# charger_and_dc_dc_ctrl.net
KiCad netlist of a schematic drawn in EAGLE
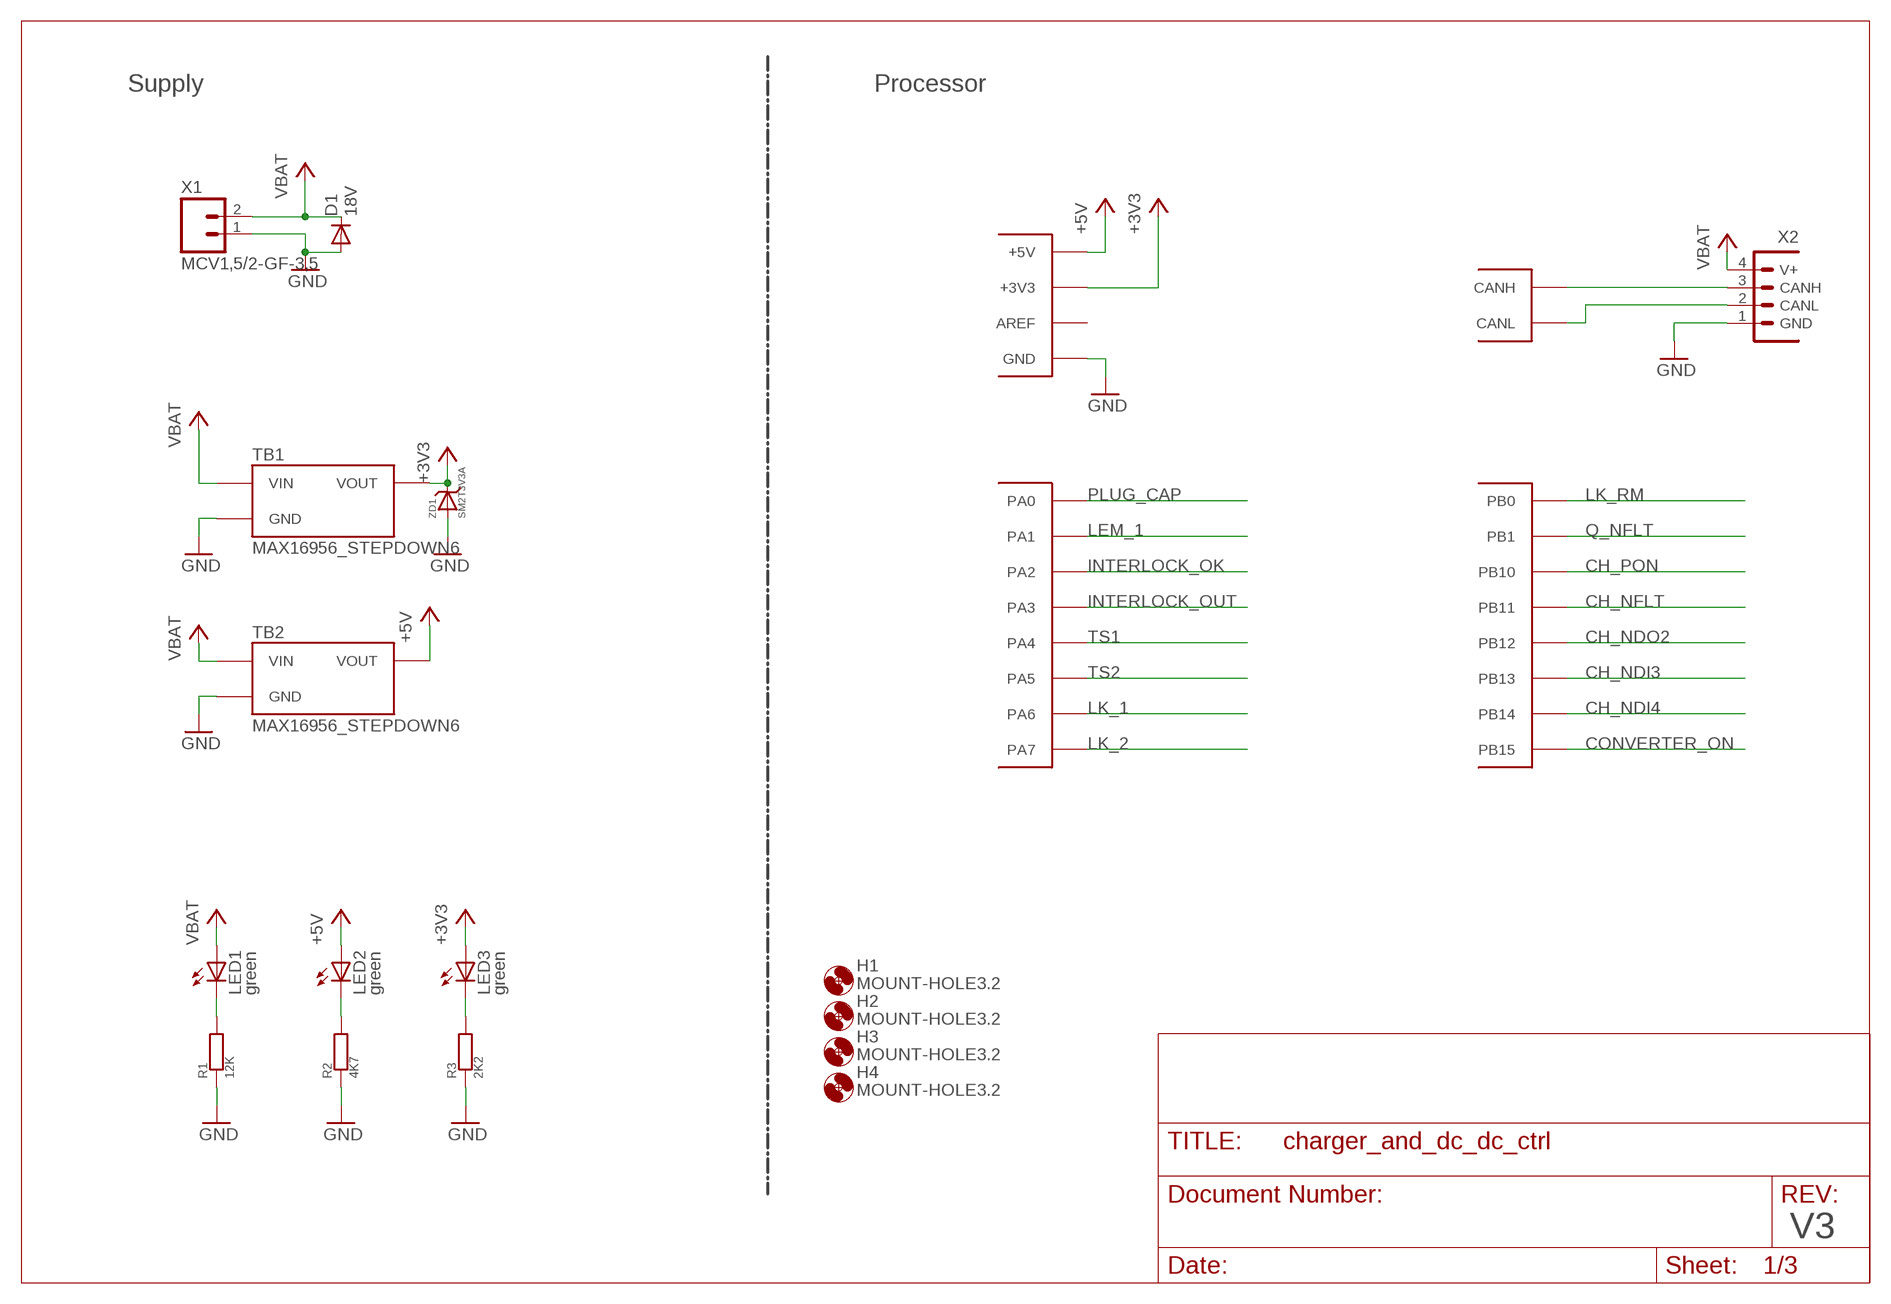
[diagram p0: schematic, sheet 1]
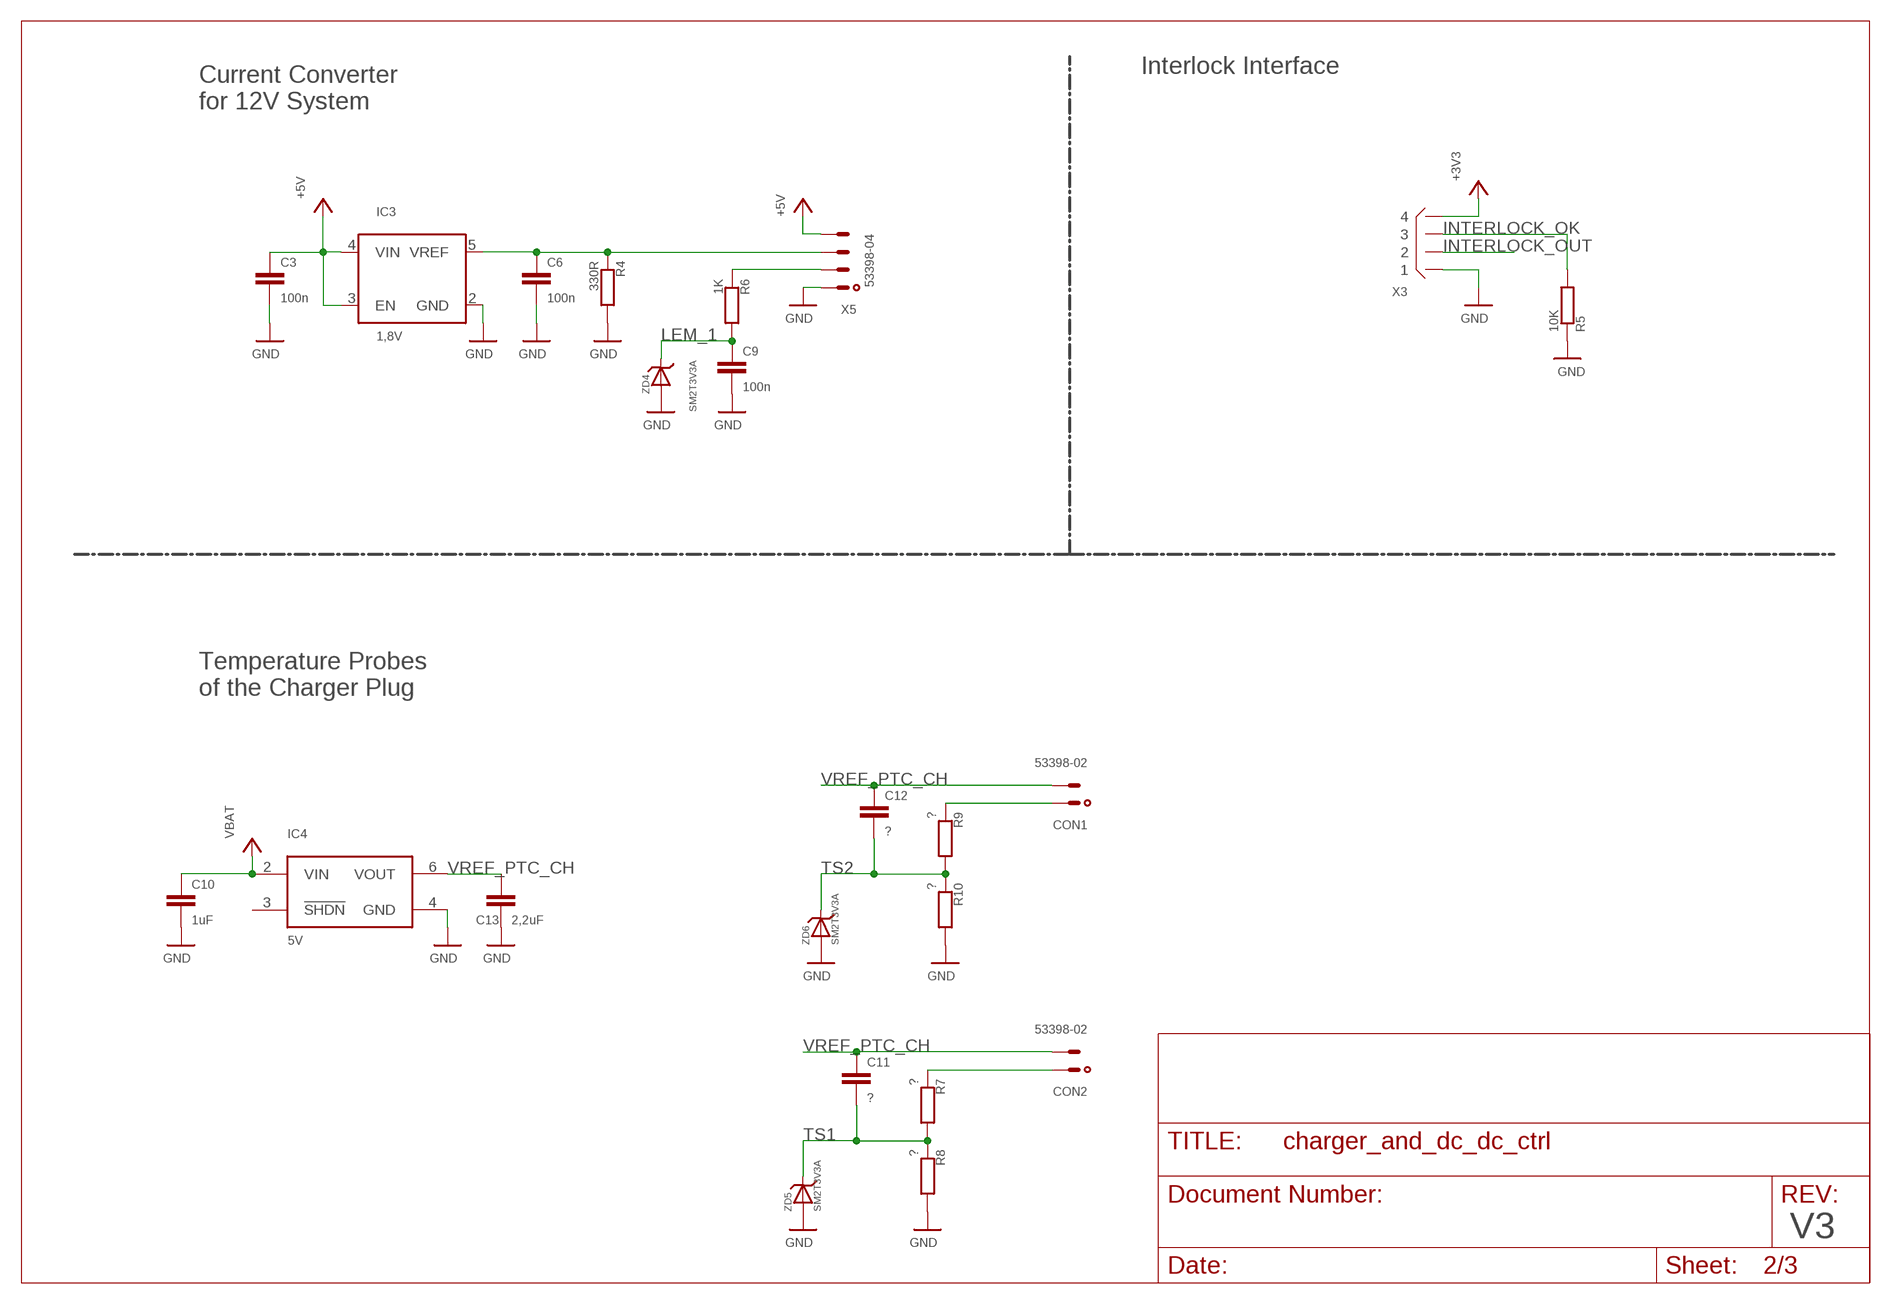
[diagram p1: schematic, sheet 2]
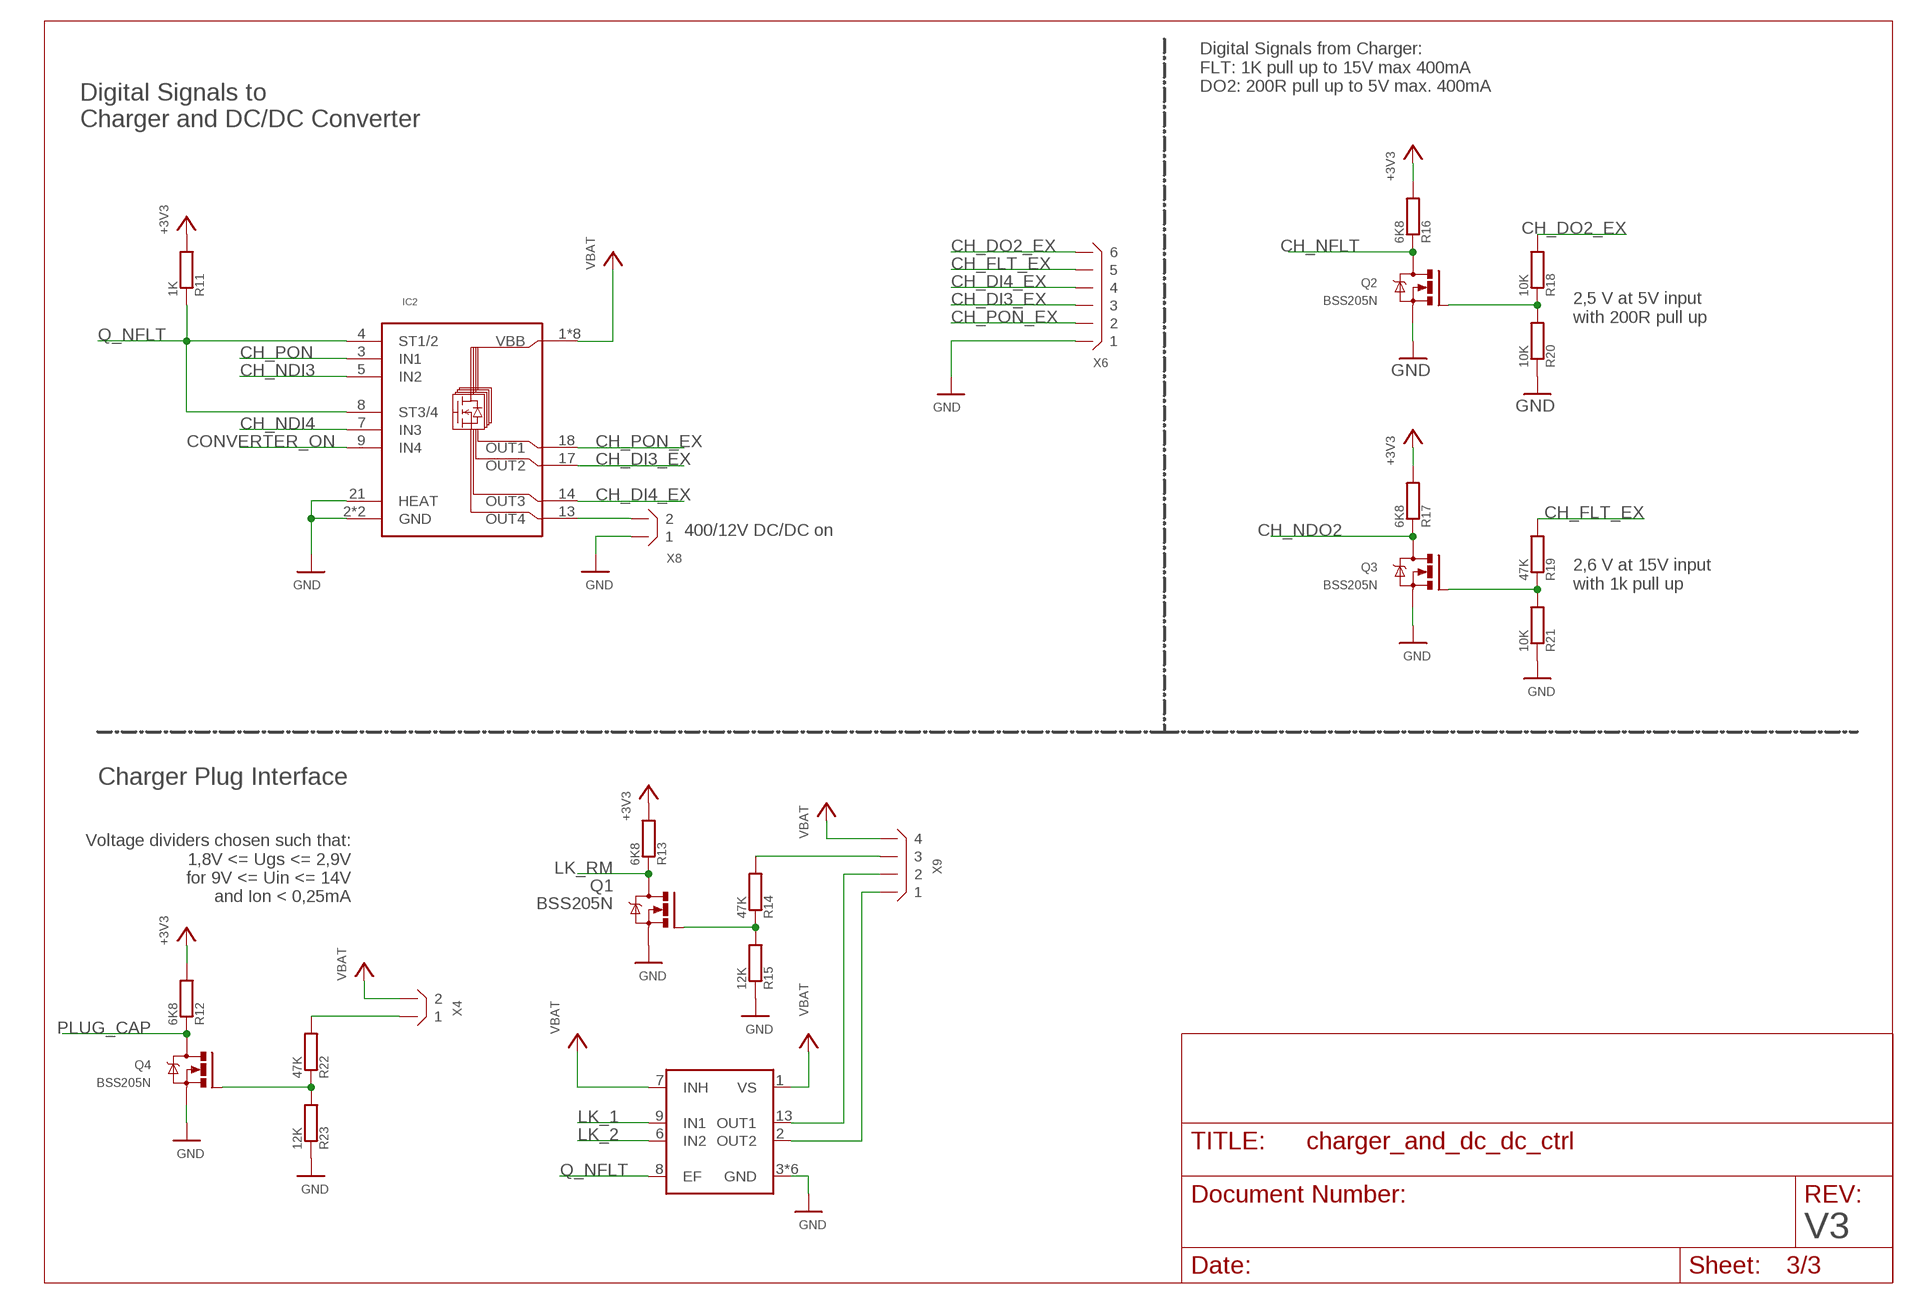
[diagram p2: schematic, sheet 3]

(export (version "E")
  (design (tool "Eeschema 10.0.6"))
  (components
    (comp (ref "CANIO_1")
      (value "STM32F103XX_CAN-IO-EXPANDERC")
      (footprint "eagle-import:STM32F103XX_CANIO-EXPANDER3")
      (libsource (lib "eagle-import") (part "STM32F103XX_CAN-IO-EXPANDERC"))
    )
    (comp (ref "D1")
      (value "18V")
      (footprint "eagle-import:DO214AA")
      (libsource (lib "eagle-import") (part "DIODE-DO214AA"))
    )
    (comp (ref "H1")
      (value "MOUNT-HOLE3.2")
      (footprint "eagle-import:3,2")
      (libsource (lib "eagle-import") (part "MOUNT-HOLE3.2"))
    )
    (comp (ref "H2")
      (value "MOUNT-HOLE3.2")
      (footprint "eagle-import:3,2")
      (libsource (lib "eagle-import") (part "MOUNT-HOLE3.2"))
    )
    (comp (ref "H3")
      (value "MOUNT-HOLE3.2")
      (footprint "eagle-import:3,2")
      (libsource (lib "eagle-import") (part "MOUNT-HOLE3.2"))
    )
    (comp (ref "H4")
      (value "MOUNT-HOLE3.2")
      (footprint "eagle-import:3,2")
      (libsource (lib "eagle-import") (part "MOUNT-HOLE3.2"))
    )
    (comp (ref "LED1")
      (value "green")
      (footprint "eagle-import:CHIP-LED0805")
      (libsource (lib "eagle-import") (part "LEDCHIP-LED0805"))
    )
    (comp (ref "LED2")
      (value "green")
      (footprint "eagle-import:CHIP-LED0805")
      (libsource (lib "eagle-import") (part "LEDCHIP-LED0805"))
    )
    (comp (ref "LED3")
      (value "green")
      (footprint "eagle-import:CHIP-LED0805")
      (libsource (lib "eagle-import") (part "LEDCHIP-LED0805"))
    )
    (comp (ref "R1")
      (value "12K")
      (footprint "eagle-import:R0805")
      (libsource (lib "eagle-import") (part "R"))
    )
    (comp (ref "R2")
      (value "4K7")
      (footprint "eagle-import:R0805")
      (libsource (lib "eagle-import") (part "R"))
    )
    (comp (ref "R3")
      (value "2K2")
      (footprint "eagle-import:R0805")
      (libsource (lib "eagle-import") (part "R"))
    )
    (comp (ref "TB1")
      (value "MAX16956_STEPDOWN6")
      (footprint "eagle-import:MAX16956_STEPDOWN6")
      (libsource (lib "eagle-import") (part "MAX16956_STEPDOWN6"))
    )
    (comp (ref "TB2")
      (value "MAX16956_STEPDOWN6")
      (footprint "eagle-import:MAX16956_STEPDOWN6")
      (libsource (lib "eagle-import") (part "MAX16956_STEPDOWN6"))
    )
    (comp (ref "X1")
      (value "MCV1,5/2-GF-3,5")
      (footprint "eagle-import:MCV1,5_2-GF-3,5")
      (libsource (lib "eagle-import") (part "MCV1,5/2-GF-3,5"))
    )
    (comp (ref "X2")
      (value "CIOC_4-1-FV-A_CAN-BELEGUNG")
      (footprint "eagle-import:CIOC_4-1-FV")
      (libsource (lib "eagle-import") (part "CIOC_4-1-FV-A_CAN-BELEGUNG"))
    )
    (comp (ref "ZD1")
      (value "SM2T3V3A")
      (footprint "eagle-import:SM2T3V3A")
      (libsource (lib "eagle-import") (part "SM2T3V3A"))
    )
    (comp (ref "IC2")
      (value "BTS716G-NEWM")
      (footprint "eagle-import:INF-PG-DSO-20-30_M_1PRIMARY")
      (libsource (lib "eagle-import") (part "BTS716G-NEWM"))
    )
    (comp (ref "IC6")
      (value "TLE4207GN")
      (footprint "eagle-import:INF-PG-DSO-14-22_N_1PRIMARY")
      (libsource (lib "eagle-import") (part "TLE4207GN"))
    )
    (comp (ref "Q1")
      (value "BSS205N")
      (footprint "eagle-import:SOT23")
      (libsource (lib "eagle-import") (part "BSS205N"))
    )
    (comp (ref "Q2")
      (value "BSS205N")
      (footprint "eagle-import:SOT23")
      (libsource (lib "eagle-import") (part "BSS205N"))
    )
    (comp (ref "Q3")
      (value "BSS205N")
      (footprint "eagle-import:SOT23")
      (libsource (lib "eagle-import") (part "BSS205N"))
    )
    (comp (ref "Q4")
      (value "BSS205N")
      (footprint "eagle-import:SOT23")
      (libsource (lib "eagle-import") (part "BSS205N"))
    )
    (comp (ref "R11")
      (value "1K")
      (footprint "eagle-import:R0603")
      (libsource (lib "eagle-import") (part "R0603"))
    )
    (comp (ref "R12")
      (value "6K8")
      (footprint "eagle-import:R0603")
      (libsource (lib "eagle-import") (part "R0603"))
    )
    (comp (ref "R13")
      (value "6K8")
      (footprint "eagle-import:R0805")
      (libsource (lib "eagle-import") (part "R"))
    )
    (comp (ref "R14")
      (value "47K")
      (footprint "eagle-import:R0805")
      (libsource (lib "eagle-import") (part "R"))
    )
    (comp (ref "R15")
      (value "12K")
      (footprint "eagle-import:R0805")
      (libsource (lib "eagle-import") (part "R"))
    )
    (comp (ref "R16")
      (value "6K8")
      (footprint "eagle-import:R0603")
      (libsource (lib "eagle-import") (part "R0603"))
    )
    (comp (ref "R17")
      (value "6K8")
      (footprint "eagle-import:R0603")
      (libsource (lib "eagle-import") (part "R0603"))
    )
    (comp (ref "R18")
      (value "10K")
      (footprint "eagle-import:R0603")
      (libsource (lib "eagle-import") (part "R0603"))
    )
    (comp (ref "R19")
      (value "47K")
      (footprint "eagle-import:R0603")
      (libsource (lib "eagle-import") (part "R0603"))
    )
    (comp (ref "R20")
      (value "10K")
      (footprint "eagle-import:R0603")
      (libsource (lib "eagle-import") (part "R0603"))
    )
    (comp (ref "R21")
      (value "10K")
      (footprint "eagle-import:R0603")
      (libsource (lib "eagle-import") (part "R0603"))
    )
    (comp (ref "R22")
      (value "47K")
      (footprint "eagle-import:R0603")
      (libsource (lib "eagle-import") (part "R0603"))
    )
    (comp (ref "R23")
      (value "12K")
      (footprint "eagle-import:R0603")
      (libsource (lib "eagle-import") (part "R0603"))
    )
    (comp (ref "X4")
      (value "B2B-XH")
      (footprint "eagle-import:B2B-XH")
      (libsource (lib "eagle-import") (part "?2B-XHB"))
    )
    (comp (ref "X6")
      (value "B6B-XH")
      (footprint "eagle-import:B6B-XH")
      (libsource (lib "eagle-import") (part "?6B-XHB"))
    )
    (comp (ref "X8")
      (value "B2B-XH")
      (footprint "eagle-import:B2B-XH")
      (libsource (lib "eagle-import") (part "?2B-XHB"))
    )
    (comp (ref "X9")
      (value "B4B-XH")
      (footprint "eagle-import:B4B-XH")
      (libsource (lib "eagle-import") (part "?4B-XHB"))
    )
    (comp (ref "C3")
      (value "100n")
      (footprint "eagle-import:C0805")
      (libsource (lib "eagle-import") (part "C-EUC0805"))
    )
    (comp (ref "C6")
      (value "100n")
      (footprint "eagle-import:C0805")
      (libsource (lib "eagle-import") (part "C-EUC0805"))
    )
    (comp (ref "C9")
      (value "100n")
      (footprint "eagle-import:C0805")
      (libsource (lib "eagle-import") (part "C-EUC0805"))
    )
    (comp (ref "C10")
      (value "1uF")
      (footprint "eagle-import:C0805")
      (libsource (lib "eagle-import") (part "C-EUC0805"))
    )
    (comp (ref "C11")
      (value "?")
      (footprint "eagle-import:C0805")
      (libsource (lib "eagle-import") (part "C-EUC0805"))
    )
    (comp (ref "C12")
      (value "?")
      (footprint "eagle-import:C0805")
      (libsource (lib "eagle-import") (part "C-EUC0805"))
    )
    (comp (ref "C13")
      (value "2,2uF")
      (footprint "eagle-import:C0805")
      (libsource (lib "eagle-import") (part "C-EUC0805"))
    )
    (comp (ref "CON1")
      (value "53398-02")
      (footprint "eagle-import:53398-02")
      (libsource (lib "eagle-import") (part "53?-02398"))
    )
    (comp (ref "CON2")
      (value "53398-02")
      (footprint "eagle-import:53398-02")
      (libsource (lib "eagle-import") (part "53?-02398"))
    )
    (comp (ref "IC3")
      (value "1,8V")
      (footprint "eagle-import:SOT23-5L")
      (libsource (lib "eagle-import") (part "LM4132L"))
    )
    (comp (ref "IC4")
      (value "5V")
      (footprint "eagle-import:SO08")
      (libsource (lib "eagle-import") (part "LT1461"))
    )
    (comp (ref "R4")
      (value "330R")
      (footprint "eagle-import:R0805")
      (libsource (lib "eagle-import") (part "R"))
    )
    (comp (ref "R5")
      (value "10K")
      (footprint "eagle-import:R0603")
      (libsource (lib "eagle-import") (part "R0603"))
    )
    (comp (ref "R6")
      (value "1K")
      (footprint "eagle-import:R0805")
      (libsource (lib "eagle-import") (part "R"))
    )
    (comp (ref "R7") (value "?") (footprint "eagle-import:R0805") (libsource (lib "eagle-import") (part "R")))
    (comp (ref "R8") (value "?") (footprint "eagle-import:R0805") (libsource (lib "eagle-import") (part "R")))
    (comp (ref "R9") (value "?") (footprint "eagle-import:R0805") (libsource (lib "eagle-import") (part "R")))
    (comp (ref "R10")
      (value "?")
      (footprint "eagle-import:R0805")
      (libsource (lib "eagle-import") (part "R"))
    )
    (comp (ref "X3")
      (value "B4B-XH")
      (footprint "eagle-import:B4B-XH")
      (libsource (lib "eagle-import") (part "?4B-XHB"))
    )
    (comp (ref "X5")
      (value "53398-04")
      (footprint "eagle-import:53398-04")
      (libsource (lib "eagle-import") (part "53?-04398"))
    )
    (comp (ref "ZD4")
      (value "SM2T3V3A")
      (footprint "eagle-import:SM2T3V3A")
      (libsource (lib "eagle-import") (part "SM2T3V3A"))
    )
    (comp (ref "ZD5")
      (value "SM2T3V3A")
      (footprint "eagle-import:SM2T3V3A")
      (libsource (lib "eagle-import") (part "SM2T3V3A"))
    )
    (comp (ref "ZD6")
      (value "SM2T3V3A")
      (footprint "eagle-import:SM2T3V3A")
      (libsource (lib "eagle-import") (part "SM2T3V3A"))
    )
  )
  (nets
    (net (code "1") (name "+3V3") (class "Default")
      (node (ref "CANIO_1") (pin "VCC") (pinfunction "+3V3_VCC") (pintype "power_in"))
      (node (ref "LED3") (pin "A") (pinfunction "A_A") (pintype "passive"))
      (node (ref "R11") (pin "2") (pinfunction "2_2") (pintype "passive"))
      (node (ref "R12") (pin "2") (pinfunction "2_2") (pintype "passive"))
      (node (ref "R13") (pin "2") (pinfunction "2_2") (pintype "passive"))
      (node (ref "R16") (pin "2") (pinfunction "2_2") (pintype "passive"))
      (node (ref "R17") (pin "2") (pinfunction "2_2") (pintype "passive"))
      (node (ref "TB1") (pin "VOUT") (pinfunction "VOUT_VOUT") (pintype "passive"))
      (node (ref "X3") (pin "P$4") (pinfunction "4_P$4") (pintype "bidirectional"))
      (node (ref "ZD1") (pin "P$2") (pinfunction "P$2_P$2") (pintype "bidirectional"))
    )
    (net (code "2") (name "+5V") (class "Default")
      (node (ref "C3") (pin "1") (pinfunction "1_1") (pintype "passive"))
      (node (ref "CANIO_1") (pin "+5V") (pinfunction "+5V_+5V") (pintype "power_in"))
      (node (ref "IC3") (pin "3") (pinfunction "EN_3") (pintype "bidirectional"))
      (node (ref "IC3") (pin "4") (pinfunction "VIN_4") (pintype "bidirectional"))
      (node (ref "LED2") (pin "A") (pinfunction "A_A") (pintype "passive"))
      (node (ref "TB2") (pin "VOUT") (pinfunction "VOUT_VOUT") (pintype "passive"))
      (node (ref "X5") (pin "4") (pinfunction "4_4") (pintype "passive"))
    )
    (net (code "3") (name "CH_DI3_EX") (class "Default")
      (node (ref "IC2") (pin "17") (pinfunction "OUT2_17") (pintype "bidirectional"))
      (node (ref "X6") (pin "P$3") (pinfunction "3_P$3") (pintype "bidirectional"))
    )
    (net (code "4") (name "CH_DI4_EX") (class "Default")
      (node (ref "IC2") (pin "14") (pinfunction "OUT3_14") (pintype "bidirectional"))
      (node (ref "X6") (pin "P$4") (pinfunction "4_P$4") (pintype "bidirectional"))
    )
    (net (code "5") (name "CH_DO2_EX") (class "Default")
      (node (ref "R18") (pin "2") (pinfunction "2_2") (pintype "passive"))
      (node (ref "X6") (pin "P$6") (pinfunction "6_P$6") (pintype "bidirectional"))
    )
    (net (code "6") (name "CH_FLT_EX") (class "Default")
      (node (ref "R19") (pin "2") (pinfunction "2_2") (pintype "passive"))
      (node (ref "X6") (pin "P$5") (pinfunction "5_P$5") (pintype "bidirectional"))
    )
    (net (code "7") (name "CH_NDI3") (class "Default")
      (node (ref "CANIO_1") (pin "PB13") (pinfunction "PB13_PB13") (pintype "bidirectional"))
      (node (ref "IC2") (pin "5") (pinfunction "IN2_5") (pintype "bidirectional"))
    )
    (net (code "8") (name "CH_NDI4") (class "Default")
      (node (ref "CANIO_1") (pin "PB14") (pinfunction "PB14_PB14") (pintype "bidirectional"))
      (node (ref "IC2") (pin "7") (pinfunction "IN3_7") (pintype "bidirectional"))
    )
    (net (code "9") (name "CH_NDO2") (class "Default")
      (node (ref "CANIO_1") (pin "PB12") (pinfunction "PB12_PB12") (pintype "bidirectional"))
      (node (ref "Q3") (pin "3") (pinfunction "D_3") (pintype "passive"))
      (node (ref "R17") (pin "1") (pinfunction "1_1") (pintype "passive"))
    )
    (net (code "10") (name "CH_NFLT") (class "Default")
      (node (ref "CANIO_1") (pin "PB11") (pinfunction "PB11_PB11") (pintype "bidirectional"))
      (node (ref "Q2") (pin "3") (pinfunction "D_3") (pintype "passive"))
      (node (ref "R16") (pin "1") (pinfunction "1_1") (pintype "passive"))
    )
    (net (code "11") (name "CH_PON") (class "Default")
      (node (ref "CANIO_1") (pin "PB10") (pinfunction "PB10_PB10") (pintype "bidirectional"))
      (node (ref "IC2") (pin "3") (pinfunction "IN1_3") (pintype "bidirectional"))
    )
    (net (code "12") (name "CH_PON_EX") (class "Default")
      (node (ref "IC2") (pin "18") (pinfunction "OUT1_18") (pintype "bidirectional"))
      (node (ref "X6") (pin "P$2") (pinfunction "2_P$2") (pintype "bidirectional"))
    )
    (net (code "13") (name "CONVERTER_ON") (class "Default")
      (node (ref "CANIO_1") (pin "PB15") (pinfunction "PB15_PB15") (pintype "bidirectional"))
      (node (ref "IC2") (pin "9") (pinfunction "IN4_9") (pintype "bidirectional"))
    )
    (net (code "14") (name "GND") (class "Default")
      (node (ref "C10") (pin "2") (pinfunction "2_2") (pintype "passive"))
      (node (ref "C13") (pin "2") (pinfunction "2_2") (pintype "passive"))
      (node (ref "C3") (pin "2") (pinfunction "2_2") (pintype "passive"))
      (node (ref "C6") (pin "2") (pinfunction "2_2") (pintype "passive"))
      (node (ref "C9") (pin "2") (pinfunction "2_2") (pintype "passive"))
      (node (ref "CANIO_1") (pin "GND1") (pinfunction "GND_GND1") (pintype "power_in"))
      (node (ref "D1") (pin "A") (pinfunction "A_A") (pintype "passive"))
      (node (ref "IC2") (pin "2") (pinfunction "GND_2") (pintype "bidirectional"))
      (node (ref "IC2") (pin "21") (pinfunction "HEAT_21") (pintype "bidirectional"))
      (node (ref "IC2") (pin "6") (pinfunction "GND_6") (pintype "bidirectional"))
      (node (ref "IC3") (pin "2") (pinfunction "GND_2") (pintype "bidirectional"))
      (node (ref "IC4") (pin "4") (pinfunction "GND_4") (pintype "power_in"))
      (node (ref "IC6") (pin "10") (pinfunction "GND_10") (pintype "bidirectional"))
      (node (ref "IC6") (pin "11") (pinfunction "GND_11") (pintype "bidirectional"))
      (node (ref "IC6") (pin "12") (pinfunction "GND_12") (pintype "bidirectional"))
      (node (ref "IC6") (pin "3") (pinfunction "GND_3") (pintype "bidirectional"))
      (node (ref "IC6") (pin "4") (pinfunction "GND_4") (pintype "bidirectional"))
      (node (ref "IC6") (pin "5") (pinfunction "GND_5") (pintype "bidirectional"))
      (node (ref "Q1") (pin "2") (pinfunction "S_2") (pintype "passive"))
      (node (ref "Q2") (pin "2") (pinfunction "S_2") (pintype "passive"))
      (node (ref "Q3") (pin "2") (pinfunction "S_2") (pintype "passive"))
      (node (ref "Q4") (pin "2") (pinfunction "S_2") (pintype "passive"))
      (node (ref "R1") (pin "1") (pinfunction "1_1") (pintype "passive"))
      (node (ref "R10") (pin "2") (pinfunction "2_2") (pintype "passive"))
      (node (ref "R15") (pin "1") (pinfunction "1_1") (pintype "passive"))
      (node (ref "R2") (pin "1") (pinfunction "1_1") (pintype "passive"))
      (node (ref "R20") (pin "1") (pinfunction "1_1") (pintype "passive"))
      (node (ref "R21") (pin "1") (pinfunction "1_1") (pintype "passive"))
      (node (ref "R23") (pin "1") (pinfunction "1_1") (pintype "passive"))
      (node (ref "R3") (pin "1") (pinfunction "1_1") (pintype "passive"))
      (node (ref "R4") (pin "2") (pinfunction "2_2") (pintype "passive"))
      (node (ref "R5") (pin "1") (pinfunction "1_1") (pintype "passive"))
      (node (ref "R8") (pin "2") (pinfunction "2_2") (pintype "passive"))
      (node (ref "TB1") (pin "GND") (pinfunction "GND_GND") (pintype "power_in"))
      (node (ref "TB1") (pin "GND2") (pinfunction "GND_GND2") (pintype "power_in"))
      (node (ref "TB2") (pin "GND") (pinfunction "GND_GND") (pintype "power_in"))
      (node (ref "TB2") (pin "GND2") (pinfunction "GND_GND2") (pintype "power_in"))
      (node (ref "X1") (pin "1") (pinfunction "1_1") (pintype "passive"))
      (node (ref "X2") (pin "1") (pinfunction "GND_1") (pintype "passive"))
      (node (ref "X3") (pin "P$1") (pinfunction "1_P$1") (pintype "bidirectional"))
      (node (ref "X5") (pin "1") (pinfunction "1_1") (pintype "passive"))
      (node (ref "X6") (pin "P$1") (pinfunction "1_P$1") (pintype "bidirectional"))
      (node (ref "X8") (pin "P$1") (pinfunction "1_P$1") (pintype "bidirectional"))
      (node (ref "ZD1") (pin "P$1") (pinfunction "P$1_P$1") (pintype "bidirectional"))
      (node (ref "ZD1") (pin "P$11") (pinfunction "P$1_P$11") (pintype "bidirectional"))
      (node (ref "ZD4") (pin "P$1") (pinfunction "P$1_P$1") (pintype "bidirectional"))
      (node (ref "ZD4") (pin "P$11") (pinfunction "P$1_P$11") (pintype "bidirectional"))
      (node (ref "ZD5") (pin "P$1") (pinfunction "P$1_P$1") (pintype "bidirectional"))
      (node (ref "ZD5") (pin "P$11") (pinfunction "P$1_P$11") (pintype "bidirectional"))
      (node (ref "ZD6") (pin "P$1") (pinfunction "P$1_P$1") (pintype "bidirectional"))
      (node (ref "ZD6") (pin "P$11") (pinfunction "P$1_P$11") (pintype "bidirectional"))
    )
    (net (code "15") (name "INTERLOCK_OK") (class "Default")
      (node (ref "CANIO_1") (pin "PA2") (pinfunction "PA2_PA2") (pintype "bidirectional"))
      (node (ref "R5") (pin "2") (pinfunction "2_2") (pintype "passive"))
      (node (ref "X3") (pin "P$3") (pinfunction "3_P$3") (pintype "bidirectional"))
    )
    (net (code "16") (name "INTERLOCK_OUT") (class "Default")
      (node (ref "CANIO_1") (pin "PA3") (pinfunction "PA3_PA3") (pintype "bidirectional"))
      (node (ref "X3") (pin "P$2") (pinfunction "2_P$2") (pintype "bidirectional"))
    )
    (net (code "17") (name "LEM_1") (class "Default")
      (node (ref "C9") (pin "1") (pinfunction "1_1") (pintype "passive"))
      (node (ref "CANIO_1") (pin "PA1") (pinfunction "PA1_PA1") (pintype "bidirectional"))
      (node (ref "R6") (pin "2") (pinfunction "2_2") (pintype "passive"))
      (node (ref "ZD4") (pin "P$2") (pinfunction "P$2_P$2") (pintype "bidirectional"))
    )
    (net (code "18") (name "LK_1") (class "Default")
      (node (ref "CANIO_1") (pin "PA6") (pinfunction "PA6_PA6") (pintype "bidirectional"))
      (node (ref "IC6") (pin "9") (pinfunction "IN1_9") (pintype "bidirectional"))
    )
    (net (code "19") (name "LK_2") (class "Default")
      (node (ref "CANIO_1") (pin "PA7") (pinfunction "PA7_PA7") (pintype "bidirectional"))
      (node (ref "IC6") (pin "6") (pinfunction "IN2_6") (pintype "bidirectional"))
    )
    (net (code "20") (name "LK_RM") (class "Default")
      (node (ref "CANIO_1") (pin "PB0") (pinfunction "PB0_PB0") (pintype "bidirectional"))
      (node (ref "Q1") (pin "3") (pinfunction "D_3") (pintype "passive"))
      (node (ref "R13") (pin "1") (pinfunction "1_1") (pintype "passive"))
    )
    (net (code "21") (name "Net-(CON1-Pad1)") (class "Default")
      (node (ref "CON1") (pin "1") (pinfunction "1_1") (pintype "passive"))
      (node (ref "R9") (pin "1") (pinfunction "1_1") (pintype "passive"))
    )
    (net (code "22") (name "Net-(CON2-Pad1)") (class "Default")
      (node (ref "CON2") (pin "1") (pinfunction "1_1") (pintype "passive"))
      (node (ref "R7") (pin "1") (pinfunction "1_1") (pintype "passive"))
    )
    (net (code "23") (name "Net-(IC2-OUT4)") (class "Default")
      (node (ref "IC2") (pin "13") (pinfunction "OUT4_13") (pintype "bidirectional"))
      (node (ref "X8") (pin "P$2") (pinfunction "2_P$2") (pintype "bidirectional"))
    )
    (net (code "24") (name "Net-(IC3-VREF)") (class "Default")
      (node (ref "C6") (pin "1") (pinfunction "1_1") (pintype "passive"))
      (node (ref "IC3") (pin "5") (pinfunction "VREF_5") (pintype "bidirectional"))
      (node (ref "R4") (pin "1") (pinfunction "1_1") (pintype "passive"))
      (node (ref "X5") (pin "3") (pinfunction "3_3") (pintype "passive"))
    )
    (net (code "25") (name "Net-(IC6-OUT1)") (class "Default")
      (node (ref "IC6") (pin "13") (pinfunction "OUT1_13") (pintype "bidirectional"))
      (node (ref "X9") (pin "P$2") (pinfunction "2_P$2") (pintype "bidirectional"))
    )
    (net (code "26") (name "Net-(IC6-OUT2)") (class "Default")
      (node (ref "IC6") (pin "2") (pinfunction "OUT2_2") (pintype "bidirectional"))
      (node (ref "X9") (pin "P$1") (pinfunction "1_P$1") (pintype "bidirectional"))
    )
    (net (code "27") (name "Net-(LED1-PadC)") (class "Default")
      (node (ref "LED1") (pin "C") (pinfunction "C_C") (pintype "passive"))
      (node (ref "R1") (pin "2") (pinfunction "2_2") (pintype "passive"))
    )
    (net (code "28") (name "Net-(LED2-PadC)") (class "Default")
      (node (ref "LED2") (pin "C") (pinfunction "C_C") (pintype "passive"))
      (node (ref "R2") (pin "2") (pinfunction "2_2") (pintype "passive"))
    )
    (net (code "29") (name "Net-(LED3-PadC)") (class "Default")
      (node (ref "LED3") (pin "C") (pinfunction "C_C") (pintype "passive"))
      (node (ref "R3") (pin "2") (pinfunction "2_2") (pintype "passive"))
    )
    (net (code "30") (name "Net-(Q1-G)") (class "Default")
      (node (ref "Q1") (pin "1") (pinfunction "G_1") (pintype "passive"))
      (node (ref "R14") (pin "1") (pinfunction "1_1") (pintype "passive"))
      (node (ref "R15") (pin "2") (pinfunction "2_2") (pintype "passive"))
    )
    (net (code "31") (name "Net-(Q2-G)") (class "Default")
      (node (ref "Q2") (pin "1") (pinfunction "G_1") (pintype "passive"))
      (node (ref "R18") (pin "1") (pinfunction "1_1") (pintype "passive"))
      (node (ref "R20") (pin "2") (pinfunction "2_2") (pintype "passive"))
    )
    (net (code "32") (name "Net-(Q3-G)") (class "Default")
      (node (ref "Q3") (pin "1") (pinfunction "G_1") (pintype "passive"))
      (node (ref "R19") (pin "1") (pinfunction "1_1") (pintype "passive"))
      (node (ref "R21") (pin "2") (pinfunction "2_2") (pintype "passive"))
    )
    (net (code "33") (name "Net-(Q4-G)") (class "Default")
      (node (ref "Q4") (pin "1") (pinfunction "G_1") (pintype "passive"))
      (node (ref "R22") (pin "1") (pinfunction "1_1") (pintype "passive"))
      (node (ref "R23") (pin "2") (pinfunction "2_2") (pintype "passive"))
    )
    (net (code "34") (name "Net-(R6-Pad1)") (class "Default")
      (node (ref "R6") (pin "1") (pinfunction "1_1") (pintype "passive"))
      (node (ref "X5") (pin "2") (pinfunction "2_2") (pintype "passive"))
    )
    (net (code "35") (name "Net-(X2-CANH)") (class "Default")
      (node (ref "CANIO_1") (pin "CANH") (pinfunction "CANH_CANH") (pintype "bidirectional"))
      (node (ref "X2") (pin "3") (pinfunction "CANH_3") (pintype "passive"))
    )
    (net (code "36") (name "Net-(X2-CANL)") (class "Default")
      (node (ref "CANIO_1") (pin "CANL") (pinfunction "CANL_CANL") (pintype "bidirectional"))
      (node (ref "X2") (pin "2") (pinfunction "CANL_2") (pintype "passive"))
    )
    (net (code "37") (name "Net-(X4-1)") (class "Default")
      (node (ref "R22") (pin "2") (pinfunction "2_2") (pintype "passive"))
      (node (ref "X4") (pin "P$1") (pinfunction "1_P$1") (pintype "bidirectional"))
    )
    (net (code "38") (name "Net-(X9-3)") (class "Default")
      (node (ref "R14") (pin "2") (pinfunction "2_2") (pintype "passive"))
      (node (ref "X9") (pin "P$3") (pinfunction "3_P$3") (pintype "bidirectional"))
    )
    (net (code "39") (name "PLUG_CAP") (class "Default")
      (node (ref "CANIO_1") (pin "PA0") (pinfunction "PA0_PA0") (pintype "bidirectional"))
      (node (ref "Q4") (pin "3") (pinfunction "D_3") (pintype "passive"))
      (node (ref "R12") (pin "1") (pinfunction "1_1") (pintype "passive"))
    )
    (net (code "40") (name "Q_NFLT") (class "Default")
      (node (ref "CANIO_1") (pin "PB1") (pinfunction "PB1_PB1") (pintype "bidirectional"))
      (node (ref "IC2") (pin "4") (pinfunction "ST1/2_4") (pintype "bidirectional"))
      (node (ref "IC2") (pin "8") (pinfunction "ST3/4_8") (pintype "bidirectional"))
      (node (ref "IC6") (pin "8") (pinfunction "EF_8") (pintype "bidirectional"))
      (node (ref "R11") (pin "1") (pinfunction "1_1") (pintype "passive"))
    )
    (net (code "41") (name "TS1") (class "Default")
      (node (ref "C11") (pin "2") (pinfunction "2_2") (pintype "passive"))
      (node (ref "CANIO_1") (pin "PA4") (pinfunction "PA4_PA4") (pintype "bidirectional"))
      (node (ref "R7") (pin "2") (pinfunction "2_2") (pintype "passive"))
      (node (ref "R8") (pin "1") (pinfunction "1_1") (pintype "passive"))
      (node (ref "ZD5") (pin "P$2") (pinfunction "P$2_P$2") (pintype "bidirectional"))
    )
    (net (code "42") (name "TS2") (class "Default")
      (node (ref "C12") (pin "2") (pinfunction "2_2") (pintype "passive"))
      (node (ref "CANIO_1") (pin "PA5") (pinfunction "PA5_PA5") (pintype "bidirectional"))
      (node (ref "R10") (pin "1") (pinfunction "1_1") (pintype "passive"))
      (node (ref "R9") (pin "2") (pinfunction "2_2") (pintype "passive"))
      (node (ref "ZD6") (pin "P$2") (pinfunction "P$2_P$2") (pintype "bidirectional"))
    )
    (net (code "43") (name "VBAT") (class "Default")
      (node (ref "C10") (pin "1") (pinfunction "1_1") (pintype "passive"))
      (node (ref "D1") (pin "C") (pinfunction "C_C") (pintype "passive"))
      (node (ref "IC2") (pin "1") (pinfunction "VBB_1") (pintype "bidirectional"))
      (node (ref "IC2") (pin "10") (pinfunction "VBB_10") (pintype "bidirectional"))
      (node (ref "IC2") (pin "11") (pinfunction "VBB_11") (pintype "bidirectional"))
      (node (ref "IC2") (pin "12") (pinfunction "VBB_12") (pintype "bidirectional"))
      (node (ref "IC2") (pin "15") (pinfunction "VBB_15") (pintype "bidirectional"))
      (node (ref "IC2") (pin "16") (pinfunction "VBB_16") (pintype "bidirectional"))
      (node (ref "IC2") (pin "19") (pinfunction "VBB_19") (pintype "bidirectional"))
      (node (ref "IC2") (pin "20") (pinfunction "VBB_20") (pintype "bidirectional"))
      (node (ref "IC4") (pin "2") (pinfunction "VIN_2") (pintype "passive"))
      (node (ref "IC6") (pin "1") (pinfunction "VS_1") (pintype "bidirectional"))
      (node (ref "IC6") (pin "7") (pinfunction "INH_7") (pintype "bidirectional"))
      (node (ref "LED1") (pin "A") (pinfunction "A_A") (pintype "passive"))
      (node (ref "TB1") (pin "VIN") (pinfunction "VIN_VIN") (pintype "passive"))
      (node (ref "TB2") (pin "VIN") (pinfunction "VIN_VIN") (pintype "passive"))
      (node (ref "X1") (pin "2") (pinfunction "2_2") (pintype "passive"))
      (node (ref "X2") (pin "4") (pinfunction "V+_4") (pintype "passive"))
      (node (ref "X4") (pin "P$2") (pinfunction "2_P$2") (pintype "bidirectional"))
      (node (ref "X9") (pin "P$4") (pinfunction "4_P$4") (pintype "bidirectional"))
    )
    (net (code "44") (name "VREF_PTC_CH") (class "Default")
      (node (ref "C11") (pin "1") (pinfunction "1_1") (pintype "passive"))
      (node (ref "C12") (pin "1") (pinfunction "1_1") (pintype "passive"))
      (node (ref "C13") (pin "1") (pinfunction "1_1") (pintype "passive"))
      (node (ref "CON1") (pin "2") (pinfunction "2_2") (pintype "passive"))
      (node (ref "CON2") (pin "2") (pinfunction "2_2") (pintype "passive"))
      (node (ref "IC4") (pin "6") (pinfunction "VOUT_6") (pintype "bidirectional"))
    )
    (net (code "45") (name "unconnected-(CANIO_1-PadAREF)") (class "Default")
      (node (ref "CANIO_1") (pin "AREF") (pinfunction "AREF_AREF") (pintype "output"))
    )
    (net (code "46") (name "unconnected-(IC4-~{SHDN}-Pad3)") (class "Default")
      (node (ref "IC4") (pin "3") (pinfunction "~{SHDN}_3") (pintype "passive"))
    )
  )
)
